# TeensyBoy_Rev1.net
KiCad netlist of a schematic drawn in EAGLE
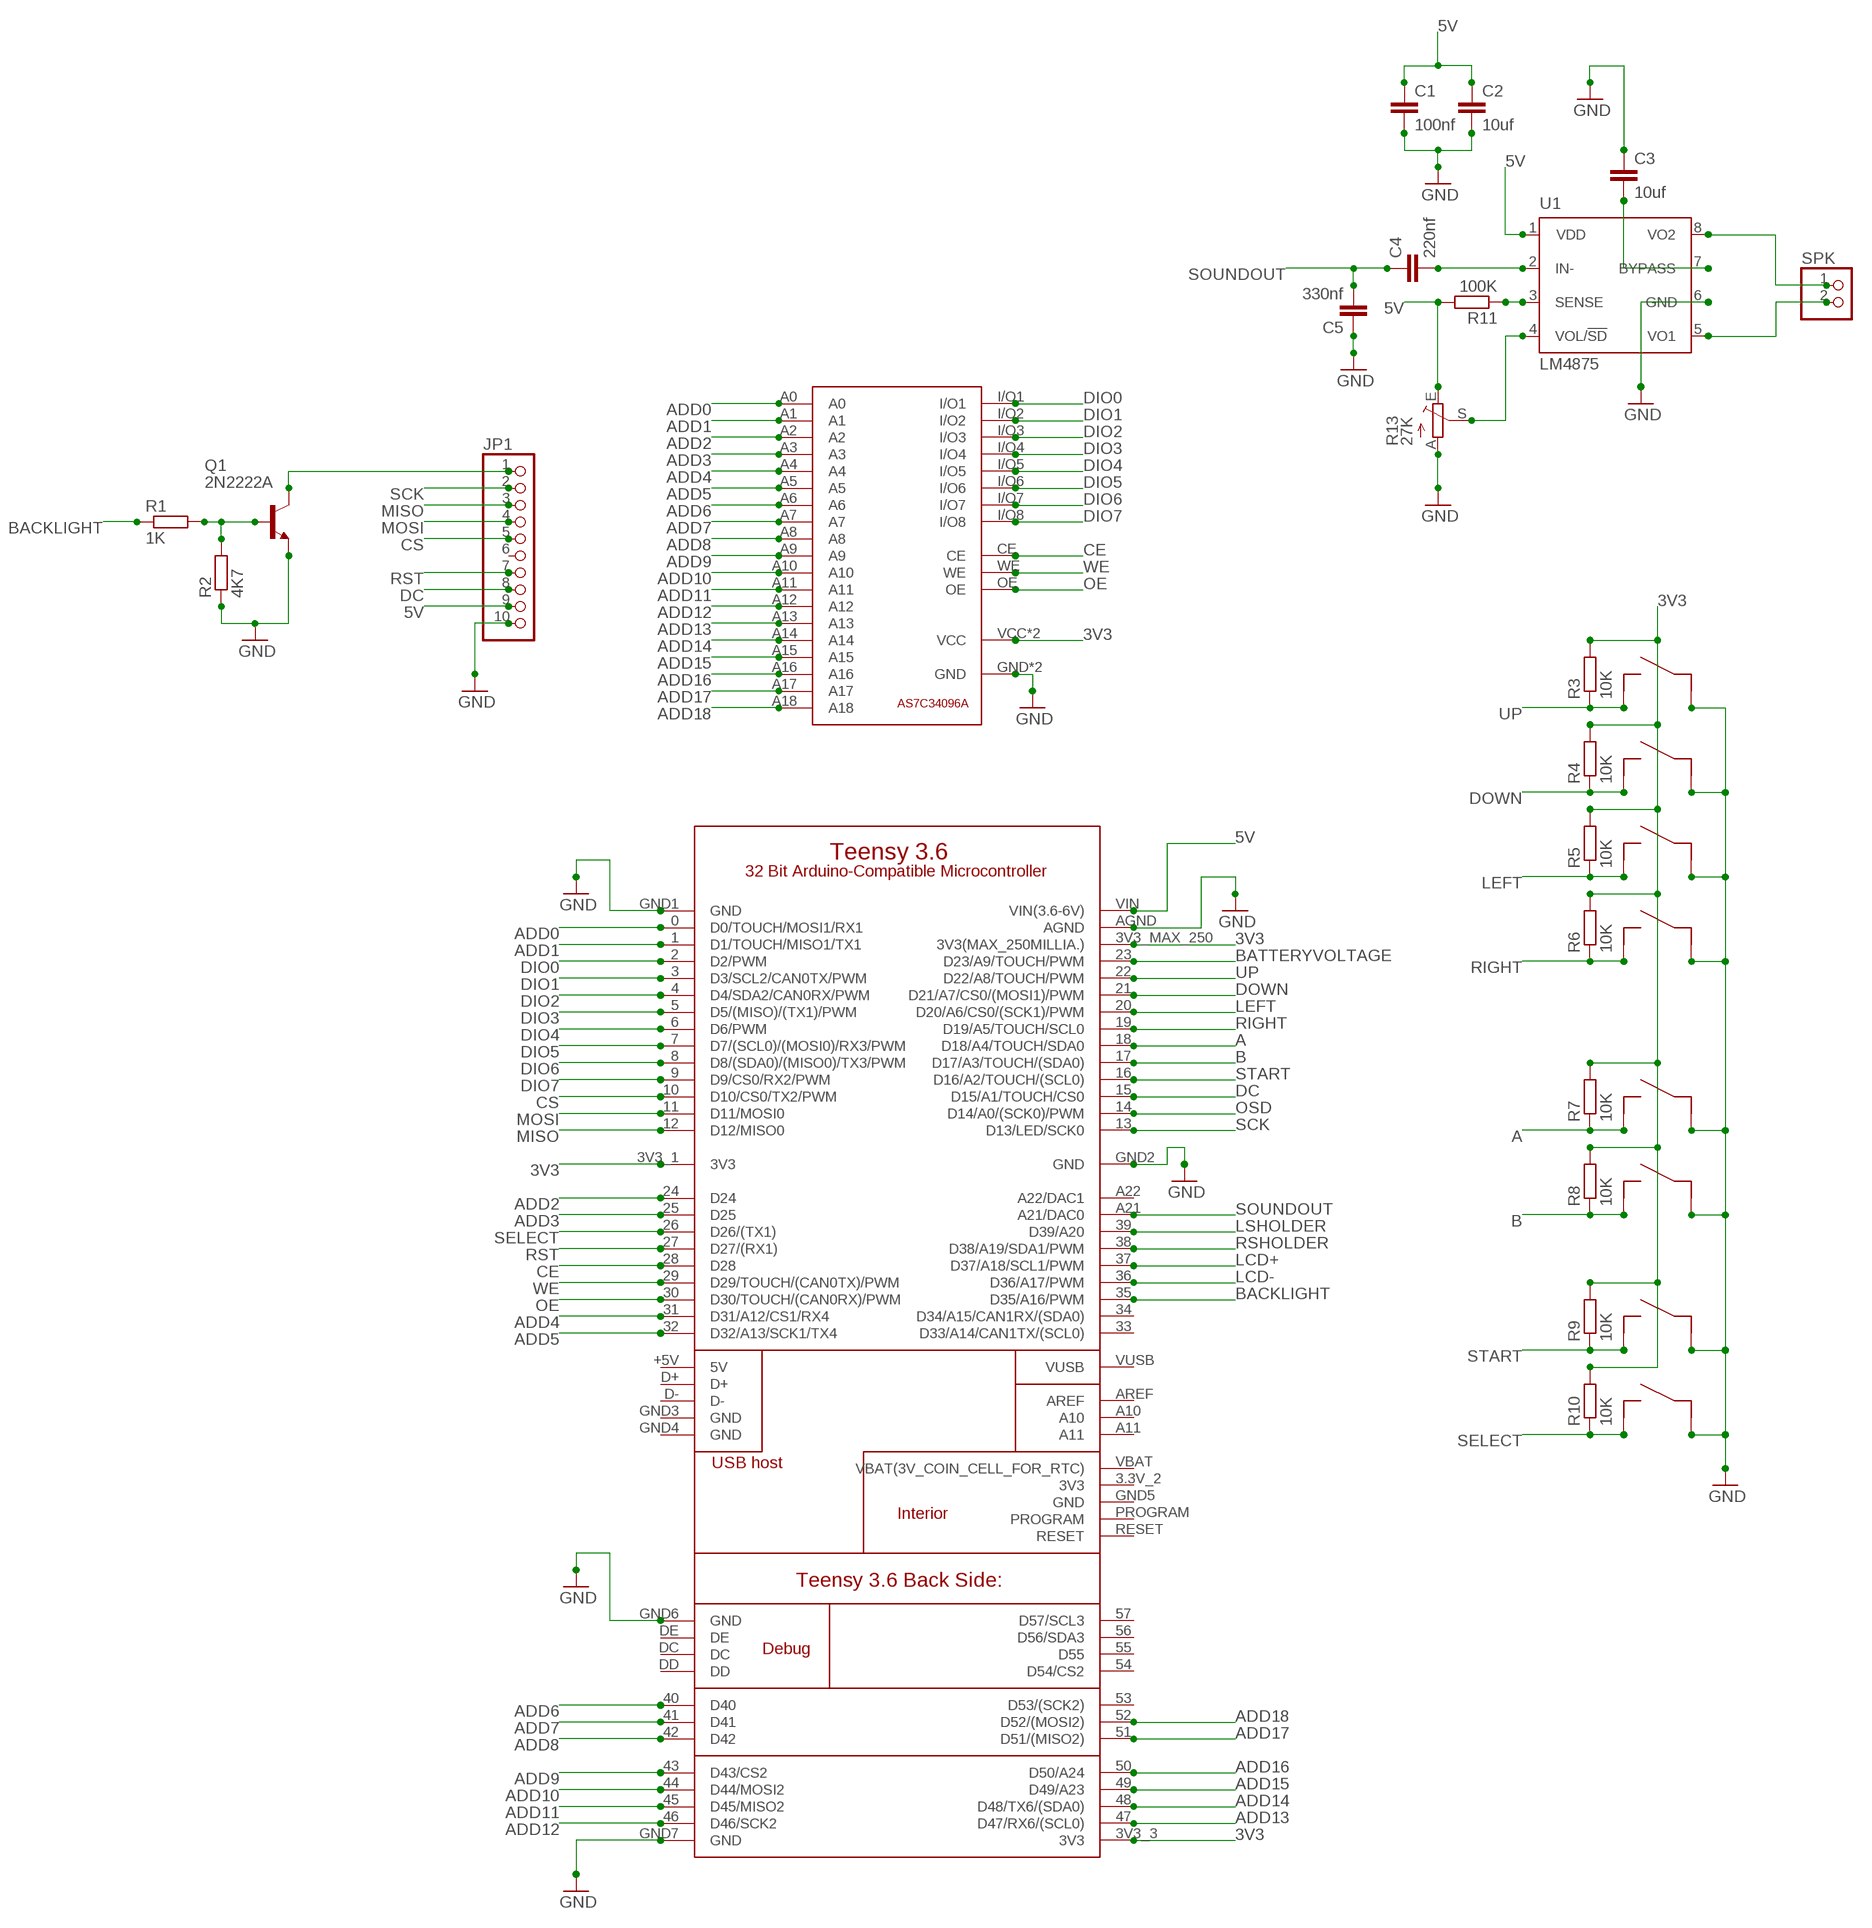
[diagram p0: schematic, sheet 1]

(export (version "E")
  (design (tool "Eeschema 10.0.6"))
  (components
    (comp (ref "A")
      (value "DTS-3")
      (footprint "eagle-import:DTS-3")
      (libsource (lib "eagle-import") (part "DTS-3"))
    )
    (comp (ref "B")
      (value "DTS-3")
      (footprint "eagle-import:DTS-3")
      (libsource (lib "eagle-import") (part "DTS-3"))
    )
    (comp (ref "C1")
      (value "100nf")
      (footprint "eagle-import:C0603K")
      (libsource (lib "eagle-import") (part "C-EUC0603K"))
    )
    (comp (ref "C2")
      (value "10uf")
      (footprint "eagle-import:C0603K")
      (libsource (lib "eagle-import") (part "C-EUC0603K"))
    )
    (comp (ref "C3")
      (value "10uf")
      (footprint "eagle-import:C0603K")
      (libsource (lib "eagle-import") (part "C-EUC0603K"))
    )
    (comp (ref "C4")
      (value "220nf")
      (footprint "eagle-import:C0603K")
      (libsource (lib "eagle-import") (part "C-EUC0603K"))
    )
    (comp (ref "C5")
      (value "330nf")
      (footprint "eagle-import:C0603K")
      (libsource (lib "eagle-import") (part "C-EUC0603K"))
    )
    (comp (ref "DOWN")
      (value "DTS-3")
      (footprint "eagle-import:DTS-3")
      (libsource (lib "eagle-import") (part "DTS-3"))
    )
    (comp (ref "JP1")
      (value "PINHD-1X10")
      (footprint "eagle-import:1X10")
      (libsource (lib "eagle-import") (part "PINHD-1X10"))
    )
    (comp (ref "LEFT")
      (value "DTS-3")
      (footprint "eagle-import:DTS-3")
      (libsource (lib "eagle-import") (part "DTS-3"))
    )
    (comp (ref "Q1")
      (value "2N2222A")
      (footprint "eagle-import:TO18")
      (libsource (lib "eagle-import") (part "2N2222A"))
    )
    (comp (ref "R1")
      (value "1K")
      (footprint "eagle-import:R0603")
      (libsource (lib "eagle-import") (part "R-EU_R0603"))
    )
    (comp (ref "R2")
      (value "4K7")
      (footprint "eagle-import:R0603")
      (libsource (lib "eagle-import") (part "R-EU_R0603"))
    )
    (comp (ref "R3")
      (value "10K")
      (footprint "eagle-import:R0603")
      (libsource (lib "eagle-import") (part "R-EU_R0603"))
    )
    (comp (ref "R4")
      (value "10K")
      (footprint "eagle-import:R0603")
      (libsource (lib "eagle-import") (part "R-EU_R0603"))
    )
    (comp (ref "R5")
      (value "10K")
      (footprint "eagle-import:R0603")
      (libsource (lib "eagle-import") (part "R-EU_R0603"))
    )
    (comp (ref "R6")
      (value "10K")
      (footprint "eagle-import:R0603")
      (libsource (lib "eagle-import") (part "R-EU_R0603"))
    )
    (comp (ref "R7")
      (value "10K")
      (footprint "eagle-import:R0603")
      (libsource (lib "eagle-import") (part "R-EU_R0603"))
    )
    (comp (ref "R8")
      (value "10K")
      (footprint "eagle-import:R0603")
      (libsource (lib "eagle-import") (part "R-EU_R0603"))
    )
    (comp (ref "R9")
      (value "10K")
      (footprint "eagle-import:R0603")
      (libsource (lib "eagle-import") (part "R-EU_R0603"))
    )
    (comp (ref "R10")
      (value "10K")
      (footprint "eagle-import:R0603")
      (libsource (lib "eagle-import") (part "R-EU_R0603"))
    )
    (comp (ref "R11")
      (value "100K")
      (footprint "eagle-import:R0603")
      (libsource (lib "eagle-import") (part "R-EU_R0603"))
    )
    (comp (ref "R13")
      (value "27K")
      (footprint "eagle-import:CT6")
      (libsource (lib "eagle-import") (part "TRIM_EU-CT6"))
    )
    (comp (ref "RIGHT")
      (value "DTS-3")
      (footprint "eagle-import:DTS-3")
      (libsource (lib "eagle-import") (part "DTS-3"))
    )
    (comp (ref "SELECT")
      (value "DTS-3")
      (footprint "eagle-import:DTS-3")
      (libsource (lib "eagle-import") (part "DTS-3"))
    )
    (comp (ref "SPK")
      (value "PINHD-1X2")
      (footprint "eagle-import:1X02")
      (libsource (lib "eagle-import") (part "PINHD-1X2"))
    )
    (comp (ref "START")
      (value "DTS-3")
      (footprint "eagle-import:DTS-3")
      (libsource (lib "eagle-import") (part "DTS-3"))
    )
    (comp (ref "U$1")
      (value "AS7C34096A")
      (footprint "eagle-import:AS7C34096A")
      (libsource (lib "eagle-import") (part "AS7C34096A"))
    )
    (comp (ref "U$2")
      (value "TEENSY-3.6_FULL")
      (footprint "eagle-import:TEENSY-3.6_FULL")
      (libsource (lib "eagle-import") (part "TEENSY-3.6_FULL"))
    )
    (comp (ref "U1")
      (value "LM4875")
      (footprint "eagle-import:SO-8")
      (libsource (lib "eagle-import") (part "LM4875"))
    )
    (comp (ref "UP")
      (value "DTS-3")
      (footprint "eagle-import:DTS-3")
      (libsource (lib "eagle-import") (part "DTS-3"))
    )
  )
  (nets
    (net (code "1") (name "/3V3") (class "Default")
      (node (ref "R10") (pin "2") (pinfunction "2_2") (pintype "passive"))
      (node (ref "R3") (pin "2") (pinfunction "2_2") (pintype "passive"))
      (node (ref "R4") (pin "2") (pinfunction "2_2") (pintype "passive"))
      (node (ref "R5") (pin "2") (pinfunction "2_2") (pintype "passive"))
      (node (ref "R6") (pin "2") (pinfunction "2_2") (pintype "passive"))
      (node (ref "R7") (pin "2") (pinfunction "2_2") (pintype "passive"))
      (node (ref "R8") (pin "2") (pinfunction "2_2") (pintype "passive"))
      (node (ref "R9") (pin "2") (pinfunction "2_2") (pintype "passive"))
      (node (ref "U$1") (pin "VCC") (pinfunction "VCC_VCC") (pintype "bidirectional"))
      (node (ref "U$1") (pin "VCC0") (pinfunction "VCC_VCC0") (pintype "bidirectional"))
      (node (ref "U$2") (pin "3V3_1") (pinfunction "3V3_3V3_1") (pintype "power_in"))
      (node (ref "U$2") (pin "3V3_3") (pinfunction "3V3_3V3_3") (pintype "bidirectional"))
      (node (ref "U$2") (pin "3V3_MAX_250") (pinfunction "3V3(MAX_250MILLIA.)_3V3_MAX_250") (pintype "bidirectional"))
    )
    (net (code "2") (name "/5V") (class "Default")
      (node (ref "C1") (pin "1") (pinfunction "1_1") (pintype "passive"))
      (node (ref "C2") (pin "1") (pinfunction "1_1") (pintype "passive"))
      (node (ref "JP1") (pin "9") (pinfunction "9_9") (pintype "passive"))
      (node (ref "R11") (pin "2") (pinfunction "2_2") (pintype "passive"))
      (node (ref "R13") (pin "E") (pinfunction "E_E") (pintype "passive"))
      (node (ref "U$2") (pin "VIN") (pinfunction "VIN(3.6-6V)_VIN") (pintype "power_in"))
      (node (ref "U1") (pin "1") (pinfunction "VDD_1") (pintype "power_in"))
    )
    (net (code "3") (name "/A") (class "Default")
      (node (ref "A") (pin "P$1") (pinfunction "P$1_P$1") (pintype "bidirectional"))
      (node (ref "R7") (pin "1") (pinfunction "1_1") (pintype "passive"))
      (node (ref "U$2") (pin "18") (pinfunction "D18/A4/TOUCH/SDA0_18") (pintype "bidirectional"))
    )
    (net (code "4") (name "/ADD0") (class "Default")
      (node (ref "U$1") (pin "A0") (pinfunction "A0_A0") (pintype "bidirectional"))
      (node (ref "U$2") (pin "0") (pinfunction "D0/TOUCH/MOSI1/RX1_0") (pintype "bidirectional"))
    )
    (net (code "5") (name "/ADD1") (class "Default")
      (node (ref "U$1") (pin "A1") (pinfunction "A1_A1") (pintype "bidirectional"))
      (node (ref "U$2") (pin "1") (pinfunction "D1/TOUCH/MISO1/TX1_1") (pintype "bidirectional"))
    )
    (net (code "6") (name "/ADD2") (class "Default")
      (node (ref "U$1") (pin "A2") (pinfunction "A2_A2") (pintype "bidirectional"))
      (node (ref "U$2") (pin "24") (pinfunction "D24_24") (pintype "bidirectional"))
    )
    (net (code "7") (name "/ADD3") (class "Default")
      (node (ref "U$1") (pin "A3") (pinfunction "A3_A3") (pintype "bidirectional"))
      (node (ref "U$2") (pin "25") (pinfunction "D25_25") (pintype "bidirectional"))
    )
    (net (code "8") (name "/ADD4") (class "Default")
      (node (ref "U$1") (pin "A4") (pinfunction "A4_A4") (pintype "bidirectional"))
      (node (ref "U$2") (pin "31") (pinfunction "D31/A12/CS1/RX4_31") (pintype "bidirectional"))
    )
    (net (code "9") (name "/ADD5") (class "Default")
      (node (ref "U$1") (pin "A5") (pinfunction "A5_A5") (pintype "bidirectional"))
      (node (ref "U$2") (pin "32") (pinfunction "D32/A13/SCK1/TX4_32") (pintype "bidirectional"))
    )
    (net (code "10") (name "/ADD6") (class "Default")
      (node (ref "U$1") (pin "A6") (pinfunction "A6_A6") (pintype "bidirectional"))
      (node (ref "U$2") (pin "40") (pinfunction "D40_40") (pintype "bidirectional"))
    )
    (net (code "11") (name "/ADD7") (class "Default")
      (node (ref "U$1") (pin "A7") (pinfunction "A7_A7") (pintype "bidirectional"))
      (node (ref "U$2") (pin "41") (pinfunction "D41_41") (pintype "bidirectional"))
    )
    (net (code "12") (name "/ADD8") (class "Default")
      (node (ref "U$1") (pin "A8") (pinfunction "A8_A8") (pintype "bidirectional"))
      (node (ref "U$2") (pin "42") (pinfunction "D42_42") (pintype "bidirectional"))
    )
    (net (code "13") (name "/ADD9") (class "Default")
      (node (ref "U$1") (pin "A9") (pinfunction "A9_A9") (pintype "bidirectional"))
      (node (ref "U$2") (pin "43") (pinfunction "D43/CS2_43") (pintype "bidirectional"))
    )
    (net (code "14") (name "/ADD10") (class "Default")
      (node (ref "U$1") (pin "A10") (pinfunction "A10_A10") (pintype "bidirectional"))
      (node (ref "U$2") (pin "44") (pinfunction "D44/MOSI2_44") (pintype "bidirectional"))
    )
    (net (code "15") (name "/ADD11") (class "Default")
      (node (ref "U$1") (pin "A11") (pinfunction "A11_A11") (pintype "bidirectional"))
      (node (ref "U$2") (pin "45") (pinfunction "D45/MISO2_45") (pintype "bidirectional"))
    )
    (net (code "16") (name "/ADD12") (class "Default")
      (node (ref "U$1") (pin "A12") (pinfunction "A12_A12") (pintype "bidirectional"))
      (node (ref "U$2") (pin "46") (pinfunction "D46/SCK2_46") (pintype "bidirectional"))
    )
    (net (code "17") (name "/ADD13") (class "Default")
      (node (ref "U$1") (pin "A13") (pinfunction "A13_A13") (pintype "bidirectional"))
      (node (ref "U$2") (pin "47") (pinfunction "D47/RX6/(SCL0)_47") (pintype "bidirectional"))
    )
    (net (code "18") (name "/ADD14") (class "Default")
      (node (ref "U$1") (pin "A14") (pinfunction "A14_A14") (pintype "bidirectional"))
      (node (ref "U$2") (pin "48") (pinfunction "D48/TX6/(SDA0)_48") (pintype "bidirectional"))
    )
    (net (code "19") (name "/ADD15") (class "Default")
      (node (ref "U$1") (pin "A15") (pinfunction "A15_A15") (pintype "bidirectional"))
      (node (ref "U$2") (pin "49") (pinfunction "D49/A23_49") (pintype "bidirectional"))
    )
    (net (code "20") (name "/ADD16") (class "Default")
      (node (ref "U$1") (pin "A16") (pinfunction "A16_A16") (pintype "bidirectional"))
      (node (ref "U$2") (pin "50") (pinfunction "D50/A24_50") (pintype "bidirectional"))
    )
    (net (code "21") (name "/ADD17") (class "Default")
      (node (ref "U$1") (pin "A17") (pinfunction "A17_A17") (pintype "bidirectional"))
      (node (ref "U$2") (pin "51") (pinfunction "D51/(MISO2)_51") (pintype "bidirectional"))
    )
    (net (code "22") (name "/ADD18") (class "Default")
      (node (ref "U$1") (pin "A18") (pinfunction "A18_A18") (pintype "bidirectional"))
      (node (ref "U$2") (pin "52") (pinfunction "D52/(MOSI2)_52") (pintype "bidirectional"))
    )
    (net (code "23") (name "/B") (class "Default")
      (node (ref "B") (pin "P$1") (pinfunction "P$1_P$1") (pintype "bidirectional"))
      (node (ref "R8") (pin "1") (pinfunction "1_1") (pintype "passive"))
      (node (ref "U$2") (pin "17") (pinfunction "D17/A3/TOUCH/(SDA0)_17") (pintype "bidirectional"))
    )
    (net (code "24") (name "/BACKLIGHT") (class "Default")
      (node (ref "R1") (pin "1") (pinfunction "1_1") (pintype "passive"))
      (node (ref "U$2") (pin "35") (pinfunction "D35/A16/PWM_35") (pintype "bidirectional"))
    )
    (net (code "25") (name "/BATTERYVOLTAGE") (class "Default")
      (node (ref "U$2") (pin "23") (pinfunction "D23/A9/TOUCH/PWM_23") (pintype "bidirectional"))
    )
    (net (code "26") (name "/CE") (class "Default")
      (node (ref "U$1") (pin "CE") (pinfunction "CE_CE") (pintype "bidirectional"))
      (node (ref "U$2") (pin "28") (pinfunction "D28_28") (pintype "bidirectional"))
    )
    (net (code "27") (name "/CS") (class "Default")
      (node (ref "JP1") (pin "5") (pinfunction "5_5") (pintype "passive"))
      (node (ref "U$2") (pin "10") (pinfunction "D10/CS0/TX2/PWM_10") (pintype "bidirectional"))
    )
    (net (code "28") (name "/DC") (class "Default")
      (node (ref "JP1") (pin "8") (pinfunction "8_8") (pintype "passive"))
      (node (ref "U$2") (pin "15") (pinfunction "D15/A1/TOUCH/CS0_15") (pintype "bidirectional"))
    )
    (net (code "29") (name "/DIO0") (class "Default")
      (node (ref "U$1") (pin "I/O1") (pinfunction "I/O1_I/O1") (pintype "bidirectional"))
      (node (ref "U$2") (pin "2") (pinfunction "D2/PWM_2") (pintype "bidirectional"))
    )
    (net (code "30") (name "/DIO1") (class "Default")
      (node (ref "U$1") (pin "I/O2") (pinfunction "I/O2_I/O2") (pintype "bidirectional"))
      (node (ref "U$2") (pin "3") (pinfunction "D3/SCL2/CAN0TX/PWM_3") (pintype "bidirectional"))
    )
    (net (code "31") (name "/DIO2") (class "Default")
      (node (ref "U$1") (pin "I/O3") (pinfunction "I/O3_I/O3") (pintype "bidirectional"))
      (node (ref "U$2") (pin "4") (pinfunction "D4/SDA2/CAN0RX/PWM_4") (pintype "bidirectional"))
    )
    (net (code "32") (name "/DIO3") (class "Default")
      (node (ref "U$1") (pin "I/O4") (pinfunction "I/O4_I/O4") (pintype "bidirectional"))
      (node (ref "U$2") (pin "5") (pinfunction "D5/(MISO)/(TX1)/PWM_5") (pintype "bidirectional"))
    )
    (net (code "33") (name "/DIO4") (class "Default")
      (node (ref "U$1") (pin "I/O5") (pinfunction "I/O5_I/O5") (pintype "bidirectional"))
      (node (ref "U$2") (pin "6") (pinfunction "D6/PWM_6") (pintype "bidirectional"))
    )
    (net (code "34") (name "/DIO5") (class "Default")
      (node (ref "U$1") (pin "I/O6") (pinfunction "I/O6_I/O6") (pintype "bidirectional"))
      (node (ref "U$2") (pin "7") (pinfunction "D7/(SCL0)/(MOSI0)/RX3/PWM_7") (pintype "bidirectional"))
    )
    (net (code "35") (name "/DIO6") (class "Default")
      (node (ref "U$1") (pin "I/O7") (pinfunction "I/O7_I/O7") (pintype "bidirectional"))
      (node (ref "U$2") (pin "8") (pinfunction "D8/(SDA0)/(MISO0)/TX3/PWM_8") (pintype "bidirectional"))
    )
    (net (code "36") (name "/DIO7") (class "Default")
      (node (ref "U$1") (pin "I/O8") (pinfunction "I/O8_I/O8") (pintype "bidirectional"))
      (node (ref "U$2") (pin "9") (pinfunction "D9/CS0/RX2/PWM_9") (pintype "bidirectional"))
    )
    (net (code "37") (name "/DOWN") (class "Default")
      (node (ref "DOWN") (pin "P$1") (pinfunction "P$1_P$1") (pintype "bidirectional"))
      (node (ref "R4") (pin "1") (pinfunction "1_1") (pintype "passive"))
      (node (ref "U$2") (pin "21") (pinfunction "D21/A7/CS0/(MOSI1)/PWM_21") (pintype "bidirectional"))
    )
    (net (code "38") (name "/LCD+") (class "Default")
      (node (ref "U$2") (pin "37") (pinfunction "D37/A18/SCL1/PWM_37") (pintype "bidirectional"))
    )
    (net (code "39") (name "/LCD-") (class "Default")
      (node (ref "U$2") (pin "36") (pinfunction "D36/A17/PWM_36") (pintype "bidirectional"))
    )
    (net (code "40") (name "/LEFT") (class "Default")
      (node (ref "LEFT") (pin "P$1") (pinfunction "P$1_P$1") (pintype "bidirectional"))
      (node (ref "R5") (pin "1") (pinfunction "1_1") (pintype "passive"))
      (node (ref "U$2") (pin "20") (pinfunction "D20/A6/CS0/(SCK1)/PWM_20") (pintype "bidirectional"))
    )
    (net (code "41") (name "/LSHOLDER") (class "Default")
      (node (ref "U$2") (pin "39") (pinfunction "D39/A20_39") (pintype "bidirectional"))
    )
    (net (code "42") (name "/MISO") (class "Default")
      (node (ref "JP1") (pin "3") (pinfunction "3_3") (pintype "passive"))
      (node (ref "U$2") (pin "12") (pinfunction "D12/MISO0_12") (pintype "bidirectional"))
    )
    (net (code "43") (name "/MOSI") (class "Default")
      (node (ref "JP1") (pin "4") (pinfunction "4_4") (pintype "passive"))
      (node (ref "U$2") (pin "11") (pinfunction "D11/MOSI0_11") (pintype "bidirectional"))
    )
    (net (code "44") (name "/OE") (class "Default")
      (node (ref "U$1") (pin "OE") (pinfunction "OE_OE") (pintype "bidirectional"))
      (node (ref "U$2") (pin "30") (pinfunction "D30/TOUCH/(CAN0RX)/PWM_30") (pintype "bidirectional"))
    )
    (net (code "45") (name "/OSD") (class "Default")
      (node (ref "U$2") (pin "14") (pinfunction "D14/A0/(SCK0)/PWM_14") (pintype "bidirectional"))
    )
    (net (code "46") (name "/RIGHT") (class "Default")
      (node (ref "R6") (pin "1") (pinfunction "1_1") (pintype "passive"))
      (node (ref "RIGHT") (pin "P$1") (pinfunction "P$1_P$1") (pintype "bidirectional"))
      (node (ref "U$2") (pin "19") (pinfunction "D19/A5/TOUCH/SCL0_19") (pintype "bidirectional"))
    )
    (net (code "47") (name "/RSHOLDER") (class "Default")
      (node (ref "U$2") (pin "38") (pinfunction "D38/A19/SDA1/PWM_38") (pintype "bidirectional"))
    )
    (net (code "48") (name "/RST") (class "Default")
      (node (ref "JP1") (pin "7") (pinfunction "7_7") (pintype "passive"))
      (node (ref "U$2") (pin "27") (pinfunction "D27/(RX1)_27") (pintype "bidirectional"))
    )
    (net (code "49") (name "/SCK") (class "Default")
      (node (ref "JP1") (pin "2") (pinfunction "2_2") (pintype "passive"))
      (node (ref "U$2") (pin "13") (pinfunction "D13/LED/SCK0_13") (pintype "bidirectional"))
    )
    (net (code "50") (name "/SELECT") (class "Default")
      (node (ref "R10") (pin "1") (pinfunction "1_1") (pintype "passive"))
      (node (ref "SELECT") (pin "P$1") (pinfunction "P$1_P$1") (pintype "bidirectional"))
      (node (ref "U$2") (pin "26") (pinfunction "D26/(TX1)_26") (pintype "bidirectional"))
    )
    (net (code "51") (name "/SOUNDOUT") (class "Default")
      (node (ref "C4") (pin "1") (pinfunction "1_1") (pintype "passive"))
      (node (ref "C5") (pin "2") (pinfunction "2_2") (pintype "passive"))
      (node (ref "U$2") (pin "A21") (pinfunction "A21/DAC0_A21") (pintype "bidirectional"))
    )
    (net (code "52") (name "/START") (class "Default")
      (node (ref "R9") (pin "1") (pinfunction "1_1") (pintype "passive"))
      (node (ref "START") (pin "P$1") (pinfunction "P$1_P$1") (pintype "bidirectional"))
      (node (ref "U$2") (pin "16") (pinfunction "D16/A2/TOUCH/(SCL0)_16") (pintype "bidirectional"))
    )
    (net (code "53") (name "/UP") (class "Default")
      (node (ref "R3") (pin "1") (pinfunction "1_1") (pintype "passive"))
      (node (ref "U$2") (pin "22") (pinfunction "D22/A8/TOUCH/PWM_22") (pintype "bidirectional"))
      (node (ref "UP") (pin "P$1") (pinfunction "P$1_P$1") (pintype "bidirectional"))
    )
    (net (code "54") (name "/WE") (class "Default")
      (node (ref "U$1") (pin "WE") (pinfunction "WE_WE") (pintype "bidirectional"))
      (node (ref "U$2") (pin "29") (pinfunction "D29/TOUCH/(CAN0TX)/PWM_29") (pintype "bidirectional"))
    )
    (net (code "55") (name "GND") (class "Default")
      (node (ref "A") (pin "P$2") (pinfunction "P$2_P$2") (pintype "bidirectional"))
      (node (ref "B") (pin "P$2") (pinfunction "P$2_P$2") (pintype "bidirectional"))
      (node (ref "C1") (pin "2") (pinfunction "2_2") (pintype "passive"))
      (node (ref "C2") (pin "2") (pinfunction "2_2") (pintype "passive"))
      (node (ref "C3") (pin "1") (pinfunction "1_1") (pintype "passive"))
      (node (ref "C5") (pin "1") (pinfunction "1_1") (pintype "passive"))
      (node (ref "DOWN") (pin "P$2") (pinfunction "P$2_P$2") (pintype "bidirectional"))
      (node (ref "JP1") (pin "10") (pinfunction "10_10") (pintype "passive"))
      (node (ref "LEFT") (pin "P$2") (pinfunction "P$2_P$2") (pintype "bidirectional"))
      (node (ref "Q1") (pin "1") (pinfunction "E_1") (pintype "passive"))
      (node (ref "R13") (pin "A") (pinfunction "A_A") (pintype "passive"))
      (node (ref "R2") (pin "1") (pinfunction "1_1") (pintype "passive"))
      (node (ref "RIGHT") (pin "P$2") (pinfunction "P$2_P$2") (pintype "bidirectional"))
      (node (ref "SELECT") (pin "P$2") (pinfunction "P$2_P$2") (pintype "bidirectional"))
      (node (ref "START") (pin "P$2") (pinfunction "P$2_P$2") (pintype "bidirectional"))
      (node (ref "U$1") (pin "GND") (pinfunction "GND_GND") (pintype "bidirectional"))
      (node (ref "U$1") (pin "GND0") (pinfunction "GND_GND0") (pintype "bidirectional"))
      (node (ref "U$2") (pin "AGND") (pinfunction "AGND_AGND") (pintype "power_in"))
      (node (ref "U$2") (pin "GND1") (pinfunction "GND_GND1") (pintype "power_in"))
      (node (ref "U$2") (pin "GND2") (pinfunction "GND_GND2") (pintype "power_in"))
      (node (ref "U$2") (pin "GND6") (pinfunction "GND_GND6") (pintype "bidirectional"))
      (node (ref "U$2") (pin "GND7") (pinfunction "GND_GND7") (pintype "bidirectional"))
      (node (ref "U1") (pin "6") (pinfunction "GND_6") (pintype "power_in"))
      (node (ref "UP") (pin "P$2") (pinfunction "P$2_P$2") (pintype "bidirectional"))
    )
    (net (code "56") (name "Net-(Q1-B)") (class "Default")
      (node (ref "Q1") (pin "2") (pinfunction "B_2") (pintype "passive"))
      (node (ref "R1") (pin "2") (pinfunction "2_2") (pintype "passive"))
      (node (ref "R2") (pin "2") (pinfunction "2_2") (pintype "passive"))
    )
    (net (code "57") (name "Net-(Q1-C)") (class "Default")
      (node (ref "JP1") (pin "1") (pinfunction "1_1") (pintype "passive"))
      (node (ref "Q1") (pin "3") (pinfunction "C_3") (pintype "passive"))
    )
    (net (code "58") (name "Net-(U1-BYPASS)") (class "Default")
      (node (ref "C3") (pin "2") (pinfunction "2_2") (pintype "passive"))
      (node (ref "U1") (pin "7") (pinfunction "BYPASS_7") (pintype "passive"))
    )
    (net (code "59") (name "Net-(U1-IN-)") (class "Default")
      (node (ref "C4") (pin "2") (pinfunction "2_2") (pintype "passive"))
      (node (ref "U1") (pin "2") (pinfunction "IN-_2") (pintype "input"))
    )
    (net (code "60") (name "Net-(U1-SENSE)") (class "Default")
      (node (ref "R11") (pin "1") (pinfunction "1_1") (pintype "passive"))
      (node (ref "U1") (pin "3") (pinfunction "SENSE_3") (pintype "input"))
    )
    (net (code "61") (name "Net-(U1-VO1)") (class "Default")
      (node (ref "SPK") (pin "2") (pinfunction "2_2") (pintype "passive"))
      (node (ref "U1") (pin "5") (pinfunction "VO1_5") (pintype "output"))
    )
    (net (code "62") (name "Net-(U1-VO2)") (class "Default")
      (node (ref "SPK") (pin "1") (pinfunction "1_1") (pintype "passive"))
      (node (ref "U1") (pin "8") (pinfunction "VO2_8") (pintype "output"))
    )
    (net (code "63") (name "Net-(U1-VOL{slash}~{SD})") (class "Default")
      (node (ref "R13") (pin "S") (pinfunction "S_S") (pintype "passive"))
      (node (ref "U1") (pin "4") (pinfunction "VOL/~{SD}_4") (pintype "input"))
    )
    (net (code "64") (name "unconnected-(JP1-Pad6)") (class "Default")
      (node (ref "JP1") (pin "6") (pinfunction "6_6") (pintype "passive"))
    )
    (net (code "65") (name "unconnected-(U$2-3V3-Pad3.3V_2)") (class "Default")
      (node (ref "U$2") (pin "3.3V_2") (pinfunction "3V3_3.3V_2") (pintype "bidirectional"))
    )
    (net (code "66") (name "unconnected-(U$2-5V-Pad+5V)") (class "Default")
      (node (ref "U$2") (pin "+5V") (pinfunction "5V_+5V") (pintype "bidirectional"))
    )
    (net (code "67") (name "unconnected-(U$2-A22{slash}DAC1-PadA22)") (class "Default")
      (node (ref "U$2") (pin "A22") (pinfunction "A22/DAC1_A22") (pintype "bidirectional"))
    )
    (net (code "68") (name "unconnected-(U$2-D33{slash}A14{slash}CAN1TX{slash}(SCL0)-Pad33)") (class "Default")
      (node (ref "U$2") (pin "33") (pinfunction "D33/A14/CAN1TX/(SCL0)_33") (pintype "bidirectional"))
    )
    (net (code "69") (name "unconnected-(U$2-D34{slash}A15{slash}CAN1RX{slash}(SDA0)-Pad34)") (class "Default")
      (node (ref "U$2") (pin "34") (pinfunction "D34/A15/CAN1RX/(SDA0)_34") (pintype "bidirectional"))
    )
    (net (code "70") (name "unconnected-(U$2-D53{slash}(SCK2)-Pad53)") (class "Default")
      (node (ref "U$2") (pin "53") (pinfunction "D53/(SCK2)_53") (pintype "bidirectional"))
    )
    (net (code "71") (name "unconnected-(U$2-D54{slash}CS2-Pad54)") (class "Default")
      (node (ref "U$2") (pin "54") (pinfunction "D54/CS2_54") (pintype "bidirectional"))
    )
    (net (code "72") (name "unconnected-(U$2-D55-Pad55)") (class "Default")
      (node (ref "U$2") (pin "55") (pinfunction "D55_55") (pintype "bidirectional"))
    )
    (net (code "73") (name "unconnected-(U$2-D56{slash}SDA3-Pad56)") (class "Default")
      (node (ref "U$2") (pin "56") (pinfunction "D56/SDA3_56") (pintype "bidirectional"))
    )
    (net (code "74") (name "unconnected-(U$2-D57{slash}SCL3-Pad57)") (class "Default")
      (node (ref "U$2") (pin "57") (pinfunction "D57/SCL3_57") (pintype "bidirectional"))
    )
    (net (code "75") (name "unconnected-(U$2-GND-PadGND3)") (class "Default")
      (node (ref "U$2") (pin "GND3") (pinfunction "GND_GND3") (pintype "bidirectional"))
    )
    (net (code "76") (name "unconnected-(U$2-GND-PadGND4)") (class "Default")
      (node (ref "U$2") (pin "GND4") (pinfunction "GND_GND4") (pintype "bidirectional"))
    )
    (net (code "77") (name "unconnected-(U$2-GND-PadGND5)") (class "Default")
      (node (ref "U$2") (pin "GND5") (pinfunction "GND_GND5") (pintype "bidirectional"))
    )
    (net (code "78") (name "unconnected-(U$2-PadA10)") (class "Default")
      (node (ref "U$2") (pin "A10") (pinfunction "A10_A10") (pintype "bidirectional"))
    )
    (net (code "79") (name "unconnected-(U$2-PadA11)") (class "Default")
      (node (ref "U$2") (pin "A11") (pinfunction "A11_A11") (pintype "bidirectional"))
    )
    (net (code "80") (name "unconnected-(U$2-PadAREF)") (class "Default")
      (node (ref "U$2") (pin "AREF") (pinfunction "AREF_AREF") (pintype "bidirectional"))
    )
    (net (code "81") (name "unconnected-(U$2-PadD+)") (class "Default")
      (node (ref "U$2") (pin "D+") (pinfunction "D+_D+") (pintype "bidirectional"))
    )
    (net (code "82") (name "unconnected-(U$2-PadD-)") (class "Default")
      (node (ref "U$2") (pin "D-") (pinfunction "D-_D-") (pintype "bidirectional"))
    )
    (net (code "83") (name "unconnected-(U$2-PadDC)") (class "Default")
      (node (ref "U$2") (pin "DC") (pinfunction "DC_DC") (pintype "bidirectional"))
    )
    (net (code "84") (name "unconnected-(U$2-PadDD)") (class "Default")
      (node (ref "U$2") (pin "DD") (pinfunction "DD_DD") (pintype "bidirectional"))
    )
    (net (code "85") (name "unconnected-(U$2-PadDE)") (class "Default")
      (node (ref "U$2") (pin "DE") (pinfunction "DE_DE") (pintype "bidirectional"))
    )
    (net (code "86") (name "unconnected-(U$2-PadPROGRAM)") (class "Default")
      (node (ref "U$2") (pin "PROGRAM") (pinfunction "PROGRAM_PROGRAM") (pintype "bidirectional"))
    )
    (net (code "87") (name "unconnected-(U$2-PadRESET)") (class "Default")
      (node (ref "U$2") (pin "RESET") (pinfunction "RESET_RESET") (pintype "bidirectional"))
    )
    (net (code "88") (name "unconnected-(U$2-PadVUSB)") (class "Default")
      (node (ref "U$2") (pin "VUSB") (pinfunction "VUSB_VUSB") (pintype "bidirectional"))
    )
    (net (code "89") (name "unconnected-(U$2-VBAT(3V_COIN_CELL_FOR_RTC)-PadVBAT)") (class "Default")
      (node (ref "U$2") (pin "VBAT") (pinfunction "VBAT(3V_COIN_CELL_FOR_RTC)_VBAT") (pintype "bidirectional"))
    )
  )
)
